# 7V_BUCK_LDOs.net
KiCad netlist of a schematic drawn in Altium Designer
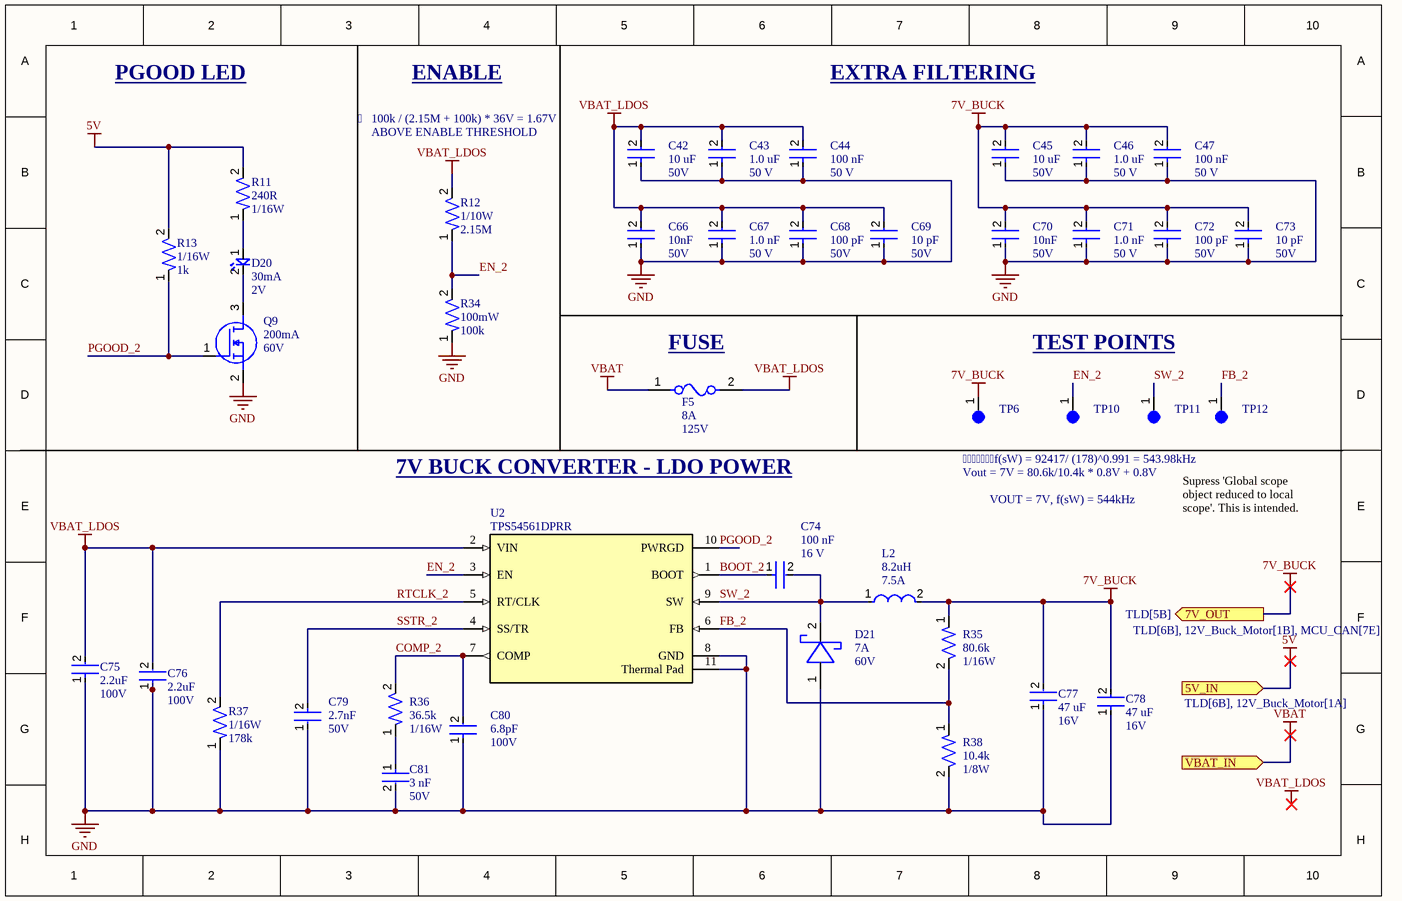
[diagram p0: 7V_BUCK_LDOs.SchDoc]

(export (version "E")
  (design (tool "Eeschema 10.0.6"))
  (components
    (comp (ref "C42")
      (value "CL32B106KBJNNNE")
      (footprint "CAP-1210")
      (description "CAP CER 10UF 50V X7R 1210")
      (fields (field (name "VOLTAGE") "50V") (field (name "CAPACITANCE") "10 uF"))
      (libsource (lib "JLC_25") (part "CAP-10U-0002"))
    )
    (comp (ref "C43")
      (value "CC0805KKX7R9BB105")
      (footprint "CAP-0805")
      (description "CAP CER 1UF 50V X7R 0805")
      (fields (field (name "VOLTAGE") "50 V") (field (name "CAPACITANCE") "1.0 uF"))
      (libsource (lib "JLC_25") (part "CAP-1U-0001"))
    )
    (comp (ref "C44")
      (value "CC0805KRX7R9BB104")
      (footprint "CAP-0805")
      (description "CAP CER 0.1UF 50V X7R 0805")
      (fields (field (name "VOLTAGE RATING") "50 V") (field (name "CAPACITANCE") "100 nF"))
      (libsource (lib "JLC_25") (part "CAP-0.1U-0002"))
    )
    (comp (ref "C45")
      (value "CL32B106KBJNNNE")
      (footprint "CAP-1210")
      (description "CAP CER 10UF 50V X7R 1210")
      (fields (field (name "VOLTAGE") "50V") (field (name "CAPACITANCE") "10 uF"))
      (libsource (lib "JLC_25") (part "CAP-10U-0002"))
    )
    (comp (ref "C46")
      (value "CC0805KKX7R9BB105")
      (footprint "CAP-0805")
      (description "CAP CER 1UF 50V X7R 0805")
      (fields (field (name "VOLTAGE") "50 V") (field (name "CAPACITANCE") "1.0 uF"))
      (libsource (lib "JLC_25") (part "CAP-1U-0001"))
    )
    (comp (ref "C47")
      (value "CC0805KRX7R9BB104")
      (footprint "CAP-0805")
      (description "CAP CER 0.1UF 50V X7R 0805")
      (fields (field (name "VOLTAGE RATING") "50 V") (field (name "CAPACITANCE") "100 nF"))
      (libsource (lib "JLC_25") (part "CAP-0.1U-0002"))
    )
    (comp (ref "C66")
      (value "GRM2195C1H103JA01D")
      (footprint "CAP-0805")
      (description "CAP CER 10000PF 50V C0G/NP0 0805")
      (fields (field (name "VOLTAGE") "50V") (field (name "CAPACITANCE") "10nF"))
      (libsource (lib "JLC_25") (part "CAP-10N-0001"))
    )
    (comp (ref "C67")
      (value "CC0402KRX7R9BB102")
      (footprint "CAP-0402")
      (description "CAP CER 1000PF 50V X7R 0402")
      (fields (field (name "VOLTAGE") "50 V") (field (name "CAPACITANCE") "1.0 nF"))
      (libsource (lib "JLC_25") (part "CAP-1N-0001"))
    )
    (comp (ref "C68")
      (value "CC0402JRNPO9BN101")
      (footprint "CAP-0402")
      (description "CAP CER 100PF 50V C0G/NPO 0402")
      (fields (field (name "CAPACITANCE") "100 pF") (field (name "VOLTAGE") "50V"))
      (libsource (lib "JLC_25") (part "CAP-100P-0001"))
    )
    (comp (ref "C69")
      (value "CC0402JRNPO9BN100")
      (footprint "CAP-0402")
      (description "CAP CER 10PF 50V C0G/NPO 0402")
      (fields (field (name "CAPACITANCE") "10 pF") (field (name "VOLTAGE") "50V"))
      (libsource (lib "JLC_25") (part "CAP-10P-0001"))
    )
    (comp (ref "C70")
      (value "GRM2195C1H103JA01D")
      (footprint "CAP-0805")
      (description "CAP CER 10000PF 50V C0G/NP0 0805")
      (fields (field (name "VOLTAGE") "50V") (field (name "CAPACITANCE") "10nF"))
      (libsource (lib "JLC_25") (part "CAP-10N-0001"))
    )
    (comp (ref "C71")
      (value "CC0402KRX7R9BB102")
      (footprint "CAP-0402")
      (description "CAP CER 1000PF 50V X7R 0402")
      (fields (field (name "VOLTAGE") "50 V") (field (name "CAPACITANCE") "1.0 nF"))
      (libsource (lib "JLC_25") (part "CAP-1N-0001"))
    )
    (comp (ref "C72")
      (value "CC0402JRNPO9BN101")
      (footprint "CAP-0402")
      (description "CAP CER 100PF 50V C0G/NPO 0402")
      (fields (field (name "CAPACITANCE") "100 pF") (field (name "VOLTAGE") "50V"))
      (libsource (lib "JLC_25") (part "CAP-100P-0001"))
    )
    (comp (ref "C73")
      (value "CC0402JRNPO9BN100")
      (footprint "CAP-0402")
      (description "CAP CER 10PF 50V C0G/NPO 0402")
      (fields (field (name "CAPACITANCE") "10 pF") (field (name "VOLTAGE") "50V"))
      (libsource (lib "JLC_25") (part "CAP-10P-0001"))
    )
    (comp (ref "C74")
      (value "CC0402KRX7R7BB104")
      (footprint "CAP-0402")
      (description "CAP CER 0.1UF 16V X7R 0402")
      (fields (field (name "VOLTAGE RATING") "16 V") (field (name "CAPACITANCE") "100 nF"))
      (libsource (lib "JLC_25") (part "CAP-0.1U-0001"))
    )
    (comp (ref "C75")
      (value "CC1206KKX7R0BB225")
      (footprint "CAP-1206")
      (description "CAP CER 2.2UF 100V X7R 1206")
      (fields (field (name "CAPACITANCE") "2.2uF") (field (name "VOLTAGE") "100V"))
      (libsource (lib "JLC_25") (part "CAP-2.2U-0001"))
    )
    (comp (ref "C76")
      (value "CC1206KKX7R0BB225")
      (footprint "CAP-1206")
      (description "CAP CER 2.2UF 100V X7R 1206")
      (fields (field (name "CAPACITANCE") "2.2uF") (field (name "VOLTAGE") "100V"))
      (libsource (lib "JLC_25") (part "CAP-2.2U-0001"))
    )
    (comp (ref "C77")
      (value "C3225X7R1N106K250AC")
      (footprint "CAP-1210")
      (description "CAP CER 47UF 16V X5R 1210")
      (fields (field (name "CAPACITANCE") "47 uF") (field (name "VOLTAGE") "16V"))
      (libsource (lib "JLC_25") (part "CAP-47U-0003"))
    )
    (comp (ref "C78")
      (value "C3225X7R1N106K250AC")
      (footprint "CAP-1210")
      (description "CAP CER 47UF 16V X5R 1210")
      (fields (field (name "CAPACITANCE") "47 uF") (field (name "VOLTAGE") "16V"))
      (libsource (lib "JLC_25") (part "CAP-47U-0003"))
    )
    (comp (ref "C79")
      (value "GRM2165C1H272JA01D")
      (footprint "CAP-0805")
      (description "CAP CER 2700PF 50V C0G/NP0 0805")
      (fields (field (name "VOLTAGE") "50V") (field (name "CAPACITANCE") "2.7nF"))
      (libsource (lib "JLC_25") (part "CAP-2.7N-0001"))
    )
    (comp (ref "C80")
      (value "CC0603CRNPO0BN6R8")
      (footprint "CAP-0603")
      (description "CAP CER 6.8PF 100V C0G/NPO 0603")
      (fields (field (name "VOLTAGE") "100V") (field (name "CAPACITANCE") "6.8pF"))
      (libsource (lib "JLC_25") (part "CAP-6.8P-0001"))
    )
    (comp (ref "C81")
      (value "GRM1885C1H302JA01D")
      (footprint "CAP-0603")
      (description "3000 pF ±5% 50V Ceramic Capacitor C0G, NP0 0603 (1608 Metric)")
      (fields (field (name "VOLTAGE") "50V") (field (name "CAPACITANCE") "3 nF"))
      (libsource (lib "JLC_25") (part "CAP-3N-0001"))
    )
    (comp (ref "D20")
      (value "BL-HKC36G-AV-TRB")
      (footprint "LED-0603")
      (description "LED YELLOW CLEAR 0603 SMD")
      (fields (field (name "FORWARD CURRENT") "30mA") (field (name "FORWARD VOLTAGE") "2V"))
      (libsource (lib "JLC_25") (part "LED-0001"))
    )
    (comp (ref "D21")
      (value "PDS760-13")
      (footprint "DO-POWERDI5")
      (description "DIODE SCHOTTKY 60V 7A POWERDI5")
      (fields (field (name "FORWARD CURRENT") "7A") (field (name "REVERSE VOLTAGE (DC)") "60V"))
      (libsource (lib "JLC_25") (part "DIO-SCHOTTKY-0001"))
    )
    (comp (ref "F5")
      (value "01550900M")
      (footprint "FUSE-0001")
      (description "FUSE BLOK CARTRIDGE 125V 10A SMD")
      (fields (field (name "FUSE CURRENT") "8A") (field (name "VOLTAGE RATING") "125V"))
      (libsource (lib "JLC_25") (part "FUSE-0001"))
    )
    (comp (ref "L2")
      (value "IHLP2525CZER8R2M01")
      (footprint "IND25X25CZ")
      (description "8.2 µH Shielded Molded Inductor 4 A 68mOhm Max Nonstandard")
      (fields (field (name "INDUCTANCE") "8.2uH") (field (name "CURRENT RATING") "7.5A"))
      (libsource (lib "JLC_25") (part "IND-8.2U-0001"))
    )
    (comp (ref "Q9")
      (value "T2N7002AK,LM")
      (footprint "IC-SOT23-3")
      (description "MOSFET N-CH 60V 200MA SOT23")
      (fields (field (name "CONTINUOUS CURRENT") "200mA") (field (name "VOLTAGE") "60V"))
      (libsource (lib "JLC_25") (part "NMOS-200MA-0001"))
    )
    (comp (ref "R11")
      (value "RC0402FR-07240RL")
      (footprint "RES-0402")
      (description "240R 0.063W 1% 0402 (1005 Metric)  SMD")
      (fields
        (field (name "TOLERANCE") "1%")
        (field (name "RESISTANCE") "240R")
        (field (name "POWER") "1/16W")
      )
      (libsource (lib "JLC_25") (part "RES-240-0001"))
    )
    (comp (ref "R12")
      (value "RC0603FR-072M15L")
      (footprint "RES-0603")
      (description "RES SMD 2.15M OHM 1% 1/10W 0603")
      (fields
        (field (name "TOLERANCE") "1%")
        (field (name "POWER") "1/10W")
        (field (name "RESISTANCE") "2.15M")
      )
      (libsource (lib "JLC_25") (part "RES-2.15M-0001"))
    )
    (comp (ref "R13")
      (value "RC0402FR-071KL")
      (footprint "RES-0402")
      (description "RES 1K OHM 1% 1/16W 0402")
      (fields (field (name "TOLERANCE") "1%") (field (name "POWER") "1/16W") (field (name "RESISTANCE") "1k"))
      (libsource (lib "JLC_25") (part "RES-1k-0001"))
    )
    (comp (ref "R34")
      (value "RC0603FR-07100KL")
      (footprint "RES-0603")
      (description "RES SMD 100K OHM 1% 1/10W 0603")
      (fields
        (field (name "TOLERANCE") "1%")
        (field (name "POWER") "100mW")
        (field (name "RESISTANCE") "100k")
      )
      (libsource (lib "JLC_25") (part "RES-100k-0001"))
    )
    (comp (ref "R35")
      (value "RC0402FR-0780K6L")
      (footprint "RES-0402")
      (description "80.6 kOhms ±1% 0.063W, 1/16W Chip Resistor 0402 (1005 Metric) Moisture Resistant Thick Film")
      (fields
        (field (name "TOLERANCE") "1%")
        (field (name "RESISTANCE") "80.6k")
        (field (name "POWER") "1/16W")
      )
      (libsource (lib "JLC_25") (part "RES-80.6k-0001"))
    )
    (comp (ref "R36")
      (value "RC0402FR-0736K5L")
      (footprint "RES-0402")
      (description "36.5 kOhms ±1% 0.063W, 1/16W Chip Resistor 0402 (1005 Metric) Moisture Resistant Thick Film")
      (fields (field (name "POWER") "1/16W") (field (name "RESISTANCE") "36.5k"))
      (libsource (lib "JLC_25") (part "RES-36.5k-0001"))
    )
    (comp (ref "R37")
      (value "RTT021783FTH")
      (footprint "RES-0402")
      (description "62.5mW Thick Film Resistors 50V ±100ppm/℃ ±1% 178kΩ 0402 Chip Resistor - Surface Mount ROHS")
      (fields
        (field (name "TOLERANCE") "1%")
        (field (name "POWER") "1/16W")
        (field (name "RESISTANCE") "178k")
      )
      (libsource (lib "JLC_25") (part "RES-178k-0001"))
    )
    (comp (ref "R38")
      (value "RT0805BRD0710K4L")
      (footprint "RES-0805")
      (description "10.4 kOhms ±0.1% 0.125W, 1/8W Chip Resistor 0805 (2012 Metric) Thin Film")
      (fields
        (field (name "TOLERANCE") "1%")
        (field (name "POWER") "1/8W")
        (field (name "RESISTANCE") "10.4k")
      )
      (libsource (lib "JLC_25") (part "RES-10.4k-0001"))
    )
    (comp (ref "TP6")
      (value "5003")
      (footprint "TEST-POINT-0001")
      (description "Oranange PC Test Point, Miniature Phoisphor Bronze Silver Plating Through Hole Mounting Type")
      (libsource (lib "*") (part "TEST-POINT-0001"))
    )
    (comp (ref "TP10")
      (value "5003")
      (footprint "TEST-POINT-0001")
      (description "Oranange PC Test Point, Miniature Phoisphor Bronze Silver Plating Through Hole Mounting Type")
      (libsource (lib "*") (part "TEST-POINT-0001"))
    )
    (comp (ref "TP11")
      (value "5003")
      (footprint "TEST-POINT-0001")
      (description "Oranange PC Test Point, Miniature Phoisphor Bronze Silver Plating Through Hole Mounting Type")
      (libsource (lib "*") (part "TEST-POINT-0001"))
    )
    (comp (ref "TP12")
      (value "5003")
      (footprint "TEST-POINT-0001")
      (description "Oranange PC Test Point, Miniature Phoisphor Bronze Silver Plating Through Hole Mounting Type")
      (libsource (lib "*") (part "TEST-POINT-0001"))
    )
    (comp (ref "U2")
      (value "TPS54561DPRR")
      (footprint "IC-10WSON")
      (description "IC REG BUCK ADJ 5A 10WSON")
      (libsource (lib "JLC_25") (part "IC-BUCK-0001"))
    )
  )
  (nets
    (net (code "1") (name "/BOOT_2") (class "Default")
      (node (ref "C74") (pin "1") (pinfunction "1_1") (pintype "passive"))
      (node (ref "U2") (pin "1") (pinfunction "BOOT_1") (pintype "output"))
    )
    (net (code "2") (name "/COMP_2") (class "Default")
      (node (ref "C80") (pin "2") (pinfunction "2_2") (pintype "passive"))
      (node (ref "R36") (pin "2") (pinfunction "2_2") (pintype "passive"))
      (node (ref "U2") (pin "7") (pinfunction "COMP_7") (pintype "output"))
    )
    (net (code "3") (name "/EN_2") (class "Default")
      (node (ref "R12") (pin "1") (pinfunction "1_1") (pintype "passive"))
      (node (ref "R34") (pin "2") (pinfunction "2_2") (pintype "passive"))
      (node (ref "TP10") (pin "1") (pinfunction "0_1") (pintype "passive"))
      (node (ref "U2") (pin "3") (pinfunction "EN_3") (pintype "input"))
    )
    (net (code "4") (name "/FB_2") (class "Default")
      (node (ref "R35") (pin "2") (pinfunction "2_2") (pintype "passive"))
      (node (ref "R38") (pin "1") (pinfunction "1_1") (pintype "passive"))
      (node (ref "TP12") (pin "1") (pinfunction "0_1") (pintype "passive"))
      (node (ref "U2") (pin "6") (pinfunction "FB_6") (pintype "input"))
    )
    (net (code "5") (name "/PGOOD_2") (class "Default")
      (node (ref "Q9") (pin "1") (pinfunction "G_1") (pintype "passive"))
      (node (ref "R13") (pin "1") (pinfunction "1_1") (pintype "passive"))
      (node (ref "U2") (pin "10") (pinfunction "PWRGD_10") (pintype "open_collector"))
    )
    (net (code "6") (name "/RTCLK_2") (class "Default")
      (node (ref "R37") (pin "2") (pinfunction "2_2") (pintype "passive"))
      (node (ref "U2") (pin "5") (pinfunction "RT/CLK_5") (pintype "input"))
    )
    (net (code "7") (name "/SSTR_2") (class "Default")
      (node (ref "C79") (pin "2") (pinfunction "2_2") (pintype "passive"))
      (node (ref "U2") (pin "4") (pinfunction "SS/TR_4") (pintype "input"))
    )
    (net (code "8") (name "/SW_2") (class "Default")
      (node (ref "C74") (pin "2") (pinfunction "2_2") (pintype "passive"))
      (node (ref "D21") (pin "2") (pinfunction "ANODE_2") (pintype "passive"))
      (node (ref "L2") (pin "1") (pinfunction "1_1") (pintype "passive"))
      (node (ref "TP11") (pin "1") (pinfunction "0_1") (pintype "passive"))
      (node (ref "U2") (pin "9") (pinfunction "SW_9") (pintype "input"))
    )
    (net (code "9") (name "5V") (class "Default")
      (node (ref "R11") (pin "2") (pinfunction "2_2") (pintype "passive"))
      (node (ref "R13") (pin "2") (pinfunction "2_2") (pintype "passive"))
    )
    (net (code "10") (name "7V_BUCK") (class "Default")
      (node (ref "C45") (pin "2") (pinfunction "2_2") (pintype "passive"))
      (node (ref "C46") (pin "2") (pinfunction "2_2") (pintype "passive"))
      (node (ref "C47") (pin "2") (pinfunction "2_2") (pintype "passive"))
      (node (ref "C70") (pin "2") (pinfunction "2_2") (pintype "passive"))
      (node (ref "C71") (pin "2") (pinfunction "2_2") (pintype "passive"))
      (node (ref "C72") (pin "2") (pinfunction "2_2") (pintype "passive"))
      (node (ref "C73") (pin "2") (pinfunction "2_2") (pintype "passive"))
      (node (ref "C77") (pin "2") (pinfunction "2_2") (pintype "passive"))
      (node (ref "C78") (pin "2") (pinfunction "2_2") (pintype "passive"))
      (node (ref "L2") (pin "2") (pinfunction "2_2") (pintype "passive"))
      (node (ref "R35") (pin "1") (pinfunction "1_1") (pintype "passive"))
      (node (ref "TP6") (pin "1") (pinfunction "0_1") (pintype "passive"))
    )
    (net (code "11") (name "GND") (class "Default")
      (node (ref "C42") (pin "1") (pinfunction "1_1") (pintype "passive"))
      (node (ref "C43") (pin "1") (pinfunction "1_1") (pintype "passive"))
      (node (ref "C44") (pin "1") (pinfunction "1_1") (pintype "passive"))
      (node (ref "C45") (pin "1") (pinfunction "1_1") (pintype "passive"))
      (node (ref "C46") (pin "1") (pinfunction "1_1") (pintype "passive"))
      (node (ref "C47") (pin "1") (pinfunction "1_1") (pintype "passive"))
      (node (ref "C66") (pin "1") (pinfunction "1_1") (pintype "passive"))
      (node (ref "C67") (pin "1") (pinfunction "1_1") (pintype "passive"))
      (node (ref "C68") (pin "1") (pinfunction "1_1") (pintype "passive"))
      (node (ref "C69") (pin "1") (pinfunction "1_1") (pintype "passive"))
      (node (ref "C70") (pin "1") (pinfunction "1_1") (pintype "passive"))
      (node (ref "C71") (pin "1") (pinfunction "1_1") (pintype "passive"))
      (node (ref "C72") (pin "1") (pinfunction "1_1") (pintype "passive"))
      (node (ref "C73") (pin "1") (pinfunction "1_1") (pintype "passive"))
      (node (ref "C75") (pin "1") (pinfunction "1_1") (pintype "passive"))
      (node (ref "C76") (pin "1") (pinfunction "1_1") (pintype "passive"))
      (node (ref "C77") (pin "1") (pinfunction "1_1") (pintype "passive"))
      (node (ref "C78") (pin "1") (pinfunction "1_1") (pintype "passive"))
      (node (ref "C79") (pin "1") (pinfunction "1_1") (pintype "passive"))
      (node (ref "C80") (pin "1") (pinfunction "1_1") (pintype "passive"))
      (node (ref "C81") (pin "2") (pinfunction "2_2") (pintype "passive"))
      (node (ref "D21") (pin "1") (pinfunction "CATHODE_1") (pintype "passive"))
      (node (ref "Q9") (pin "2") (pinfunction "S_2") (pintype "passive"))
      (node (ref "R34") (pin "1") (pinfunction "1_1") (pintype "passive"))
      (node (ref "R37") (pin "1") (pinfunction "1_1") (pintype "passive"))
      (node (ref "R38") (pin "2") (pinfunction "2_2") (pintype "passive"))
      (node (ref "U2") (pin "11") (pinfunction "Thermal_Pad_11") (pintype "power_in"))
      (node (ref "U2") (pin "8") (pinfunction "GND_8") (pintype "power_in"))
    )
    (net (code "12") (name "Net-(C81-Pad1)") (class "Default")
      (node (ref "C81") (pin "1") (pinfunction "1_1") (pintype "passive"))
      (node (ref "R36") (pin "1") (pinfunction "1_1") (pintype "passive"))
    )
    (net (code "13") (name "Net-(D20-Pad1)") (class "Default")
      (node (ref "D20") (pin "1") (pinfunction "1_1") (pintype "passive"))
      (node (ref "R11") (pin "1") (pinfunction "1_1") (pintype "passive"))
    )
    (net (code "14") (name "Net-(Q9-D)") (class "Default")
      (node (ref "D20") (pin "2") (pinfunction "2_2") (pintype "passive"))
      (node (ref "Q9") (pin "3") (pinfunction "D_3") (pintype "passive"))
    )
    (net (code "15") (name "VBAT") (class "Default")
      (node (ref "F5") (pin "1") (pinfunction "1_1") (pintype "passive"))
    )
    (net (code "16") (name "VBAT_LDOS") (class "Default")
      (node (ref "C42") (pin "2") (pinfunction "2_2") (pintype "passive"))
      (node (ref "C43") (pin "2") (pinfunction "2_2") (pintype "passive"))
      (node (ref "C44") (pin "2") (pinfunction "2_2") (pintype "passive"))
      (node (ref "C66") (pin "2") (pinfunction "2_2") (pintype "passive"))
      (node (ref "C67") (pin "2") (pinfunction "2_2") (pintype "passive"))
      (node (ref "C68") (pin "2") (pinfunction "2_2") (pintype "passive"))
      (node (ref "C69") (pin "2") (pinfunction "2_2") (pintype "passive"))
      (node (ref "C75") (pin "2") (pinfunction "2_2") (pintype "passive"))
      (node (ref "C76") (pin "2") (pinfunction "2_2") (pintype "passive"))
      (node (ref "F5") (pin "2") (pinfunction "2_2") (pintype "passive"))
      (node (ref "R12") (pin "2") (pinfunction "2_2") (pintype "passive"))
      (node (ref "U2") (pin "2") (pinfunction "VIN_2") (pintype "input"))
    )
  )
)
